# Lamp_Logic_Board_2.net
KiCad netlist of a schematic drawn in EAGLE
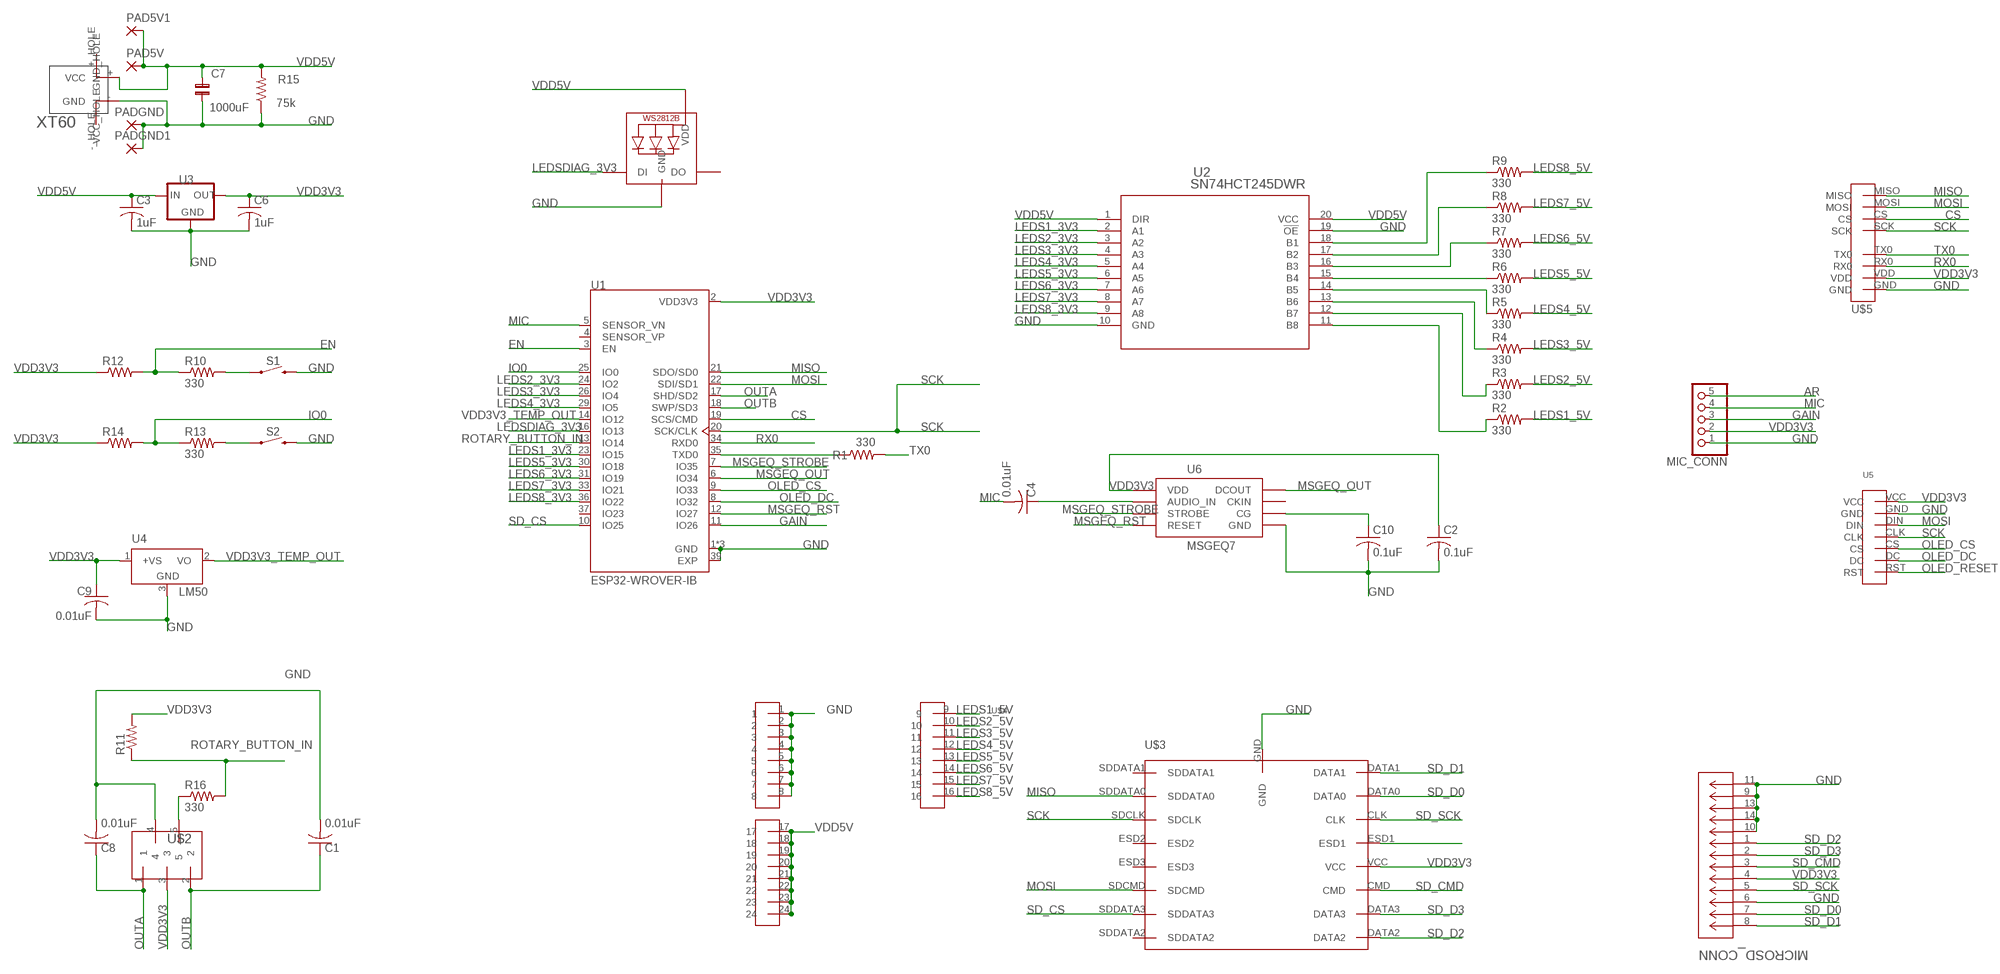
[diagram p0: schematic, sheet 1]

(export (version "E")
  (design (tool "Eeschema 10.0.6"))
  (components
    (comp (ref "C1")
      (value "0.01uF")
      (footprint "eagle-import:C0402")
      (libsource (lib "eagle-import") (part "C-USC0402"))
    )
    (comp (ref "C2")
      (value "0.1uF")
      (footprint "eagle-import:C0805")
      (libsource (lib "eagle-import") (part "C-USC0805"))
    )
    (comp (ref "C3")
      (value "1uF")
      (footprint "eagle-import:C0402")
      (libsource (lib "eagle-import") (part "C-USC0402"))
    )
    (comp (ref "C4")
      (value "0.01uF")
      (footprint "eagle-import:C0402")
      (libsource (lib "eagle-import") (part "C-USC0402"))
    )
    (comp (ref "C6")
      (value "1uF")
      (footprint "eagle-import:C0402")
      (libsource (lib "eagle-import") (part "C-USC0402"))
    )
    (comp (ref "C7")
      (value "1000uF")
      (footprint "eagle-import:ENP2,0-5")
      (libsource (lib "eagle-import") (part "C-BP-2,0X5"))
    )
    (comp (ref "C8")
      (value "0.01uF")
      (footprint "eagle-import:C0402")
      (libsource (lib "eagle-import") (part "C-USC0402"))
    )
    (comp (ref "C9")
      (value "0.01uF")
      (footprint "eagle-import:C0402")
      (libsource (lib "eagle-import") (part "C-USC0402"))
    )
    (comp (ref "C10")
      (value "0.1uF")
      (footprint "eagle-import:C0805")
      (libsource (lib "eagle-import") (part "C-USC0805"))
    )
    (comp (ref "LED1")
      (value "WS2812B5050")
      (footprint "eagle-import:WS2812B")
      (fields (field (name "MF") "Seeed Technology") (field (name "MP") "WS2812B"))
      (libsource (lib "eagle-import") (part "WS2812B5050"))
    )
    (comp (ref "MICROSD_CONN")
      (value "LLC")
      (footprint "eagle-import:CON00218_8")
      (libsource (lib "eagle-import") (part "LLC"))
    )
    (comp (ref "MIC_CONN")
      (value "PINHD-1X5")
      (footprint "eagle-import:1X05")
      (libsource (lib "eagle-import") (part "PINHD-1X5"))
    )
    (comp (ref "PAD5V")
      (value "SMD5")
      (footprint "eagle-import:SMD2,54-5,08")
      (libsource (lib "eagle-import") (part "SMD5"))
    )
    (comp (ref "PAD5V1")
      (value "SMD5")
      (footprint "eagle-import:SMD2,54-5,08")
      (libsource (lib "eagle-import") (part "SMD5"))
    )
    (comp (ref "PADGND")
      (value "SMD5")
      (footprint "eagle-import:SMD2,54-5,08")
      (libsource (lib "eagle-import") (part "SMD5"))
    )
    (comp (ref "PADGND1")
      (value "SMD5")
      (footprint "eagle-import:SMD2,54-5,08")
      (libsource (lib "eagle-import") (part "SMD5"))
    )
    (comp (ref "R1")
      (value "330")
      (footprint "eagle-import:R1206")
      (libsource (lib "eagle-import") (part "R-US_R1206"))
    )
    (comp (ref "R2")
      (value "330")
      (footprint "eagle-import:R1206")
      (libsource (lib "eagle-import") (part "R-US_R1206"))
    )
    (comp (ref "R3")
      (value "330")
      (footprint "eagle-import:R1206")
      (libsource (lib "eagle-import") (part "R-US_R1206"))
    )
    (comp (ref "R4")
      (value "330")
      (footprint "eagle-import:R1206")
      (libsource (lib "eagle-import") (part "R-US_R1206"))
    )
    (comp (ref "R5")
      (value "330")
      (footprint "eagle-import:R1206")
      (libsource (lib "eagle-import") (part "R-US_R1206"))
    )
    (comp (ref "R6")
      (value "330")
      (footprint "eagle-import:R1206")
      (libsource (lib "eagle-import") (part "R-US_R1206"))
    )
    (comp (ref "R7")
      (value "330")
      (footprint "eagle-import:R1206")
      (libsource (lib "eagle-import") (part "R-US_R1206"))
    )
    (comp (ref "R8")
      (value "330")
      (footprint "eagle-import:R1206")
      (libsource (lib "eagle-import") (part "R-US_R1206"))
    )
    (comp (ref "R9")
      (value "330")
      (footprint "eagle-import:R1206")
      (libsource (lib "eagle-import") (part "R-US_R1206"))
    )
    (comp (ref "R10")
      (value "330")
      (footprint "eagle-import:R1206")
      (libsource (lib "eagle-import") (part "R-US_R1206"))
    )
    (comp (ref "R11")
      (value "R-US_R0603")
      (footprint "eagle-import:R0603")
      (libsource (lib "eagle-import") (part "R-US_R0603"))
    )
    (comp (ref "R12")
      (value "R-US_R0603")
      (footprint "eagle-import:R0603")
      (libsource (lib "eagle-import") (part "R-US_R0603"))
    )
    (comp (ref "R13")
      (value "330")
      (footprint "eagle-import:R1206")
      (libsource (lib "eagle-import") (part "R-US_R1206"))
    )
    (comp (ref "R14")
      (value "R-US_R0603")
      (footprint "eagle-import:R0603")
      (libsource (lib "eagle-import") (part "R-US_R0603"))
    )
    (comp (ref "R15")
      (value "75k")
      (footprint "eagle-import:0309_12")
      (libsource (lib "eagle-import") (part "R-US_0309/12"))
    )
    (comp (ref "R16")
      (value "330")
      (footprint "eagle-import:R1206")
      (libsource (lib "eagle-import") (part "R-US_R1206"))
    )
    (comp (ref "S1")
      (value "MOMENTARY-SWITCH-SPST-SMD-6.0X3.5MM")
      (footprint "eagle-import:TACTILE_SWITCH_SMD_6.0X3.5MM")
      (libsource (lib "eagle-import") (part "MOMENTARY-SWITCH-SPST-SMD-6.0X3.5MM"))
    )
    (comp (ref "S2")
      (value "MOMENTARY-SWITCH-SPST-SMD-6.0X3.5MM")
      (footprint "eagle-import:TACTILE_SWITCH_SMD_6.0X3.5MM")
      (libsource (lib "eagle-import") (part "MOMENTARY-SWITCH-SPST-SMD-6.0X3.5MM"))
    )
    (comp (ref "U$1")
      (value "XT60")
      (footprint "eagle-import:XT60")
      (libsource (lib "eagle-import") (part "XT60"))
    )
    (comp (ref "U$2")
      (value "EN11-HSM1AF15")
      (footprint "eagle-import:EN11-HSM")
      (libsource (lib "eagle-import") (part "EN11-HSM1AF15"))
    )
    (comp (ref "U$3")
      (value "CM1624-08DE")
      (footprint "eagle-import:CM1624-08DE")
      (libsource (lib "eagle-import") (part "CM1624-08DE"))
    )
    (comp (ref "U$4")
      (value "3X8PINHEAD")
      (footprint "eagle-import:3X8PINHEAD")
      (libsource (lib "eagle-import") (part "3X8PINHEAD"))
    )
    (comp (ref "U$5")
      (value "2X4PINHEAD")
      (footprint "eagle-import:2X4PINHEAD")
      (libsource (lib "eagle-import") (part "2X4PINHEAD"))
    )
    (comp (ref "U1")
      (value "ESP32-WROVER-IB")
      (footprint "eagle-import:XCVR_ESP32-WROVER-I")
      (fields (field (name "MF") "Espressif Systems") (field (name "MP") "ESP32-WROVER-I"))
      (libsource (lib "eagle-import") (part "ESP32-WROVER-I"))
    )
    (comp (ref "U2")
      (value "SN74HCT245DWR")
      (footprint "eagle-import:DW20")
      (libsource (lib "eagle-import") (part "SN74HCT245DWR"))
    )
    (comp (ref "U3")
      (value "LM1117MP-1.8")
      (footprint "eagle-import:SOT223")
      (fields (field (name "MF") "Texas Instruments"))
      (libsource (lib "eagle-import") (part "LM1117?-MP1.8"))
    )
    (comp (ref "U4")
      (value "LM50")
      (footprint "eagle-import:SOT23")
      (libsource (lib "eagle-import") (part "LM50"))
    )
    (comp (ref "U5")
      (value "SPIOLED_STANDOFF")
      (footprint "eagle-import:SPIOLED_STADOFF")
      (libsource (lib "eagle-import") (part "SPIOLED_STANDOFF"))
    )
    (comp (ref "U6")
      (value "MSGEQ7DIL")
      (footprint "eagle-import:DIL-08")
      (fields
        (field (name "DIGI-KEY_PART_NUMBER") "1568-1544-ND")
        (field (name "MF") "SparkFun Electronics")
        (field (name "MP") "MSGEQ7")
      )
      (libsource (lib "eagle-import") (part "MSGEQ7DIL"))
    )
  )
  (nets
    (net (code "1") (name "/AR") (class "Default")
      (node (ref "MIC_CONN") (pin "5") (pinfunction "5_5") (pintype "passive"))
    )
    (net (code "2") (name "/CS") (class "Default")
      (node (ref "U$5") (pin "CS") (pinfunction "CS_CS") (pintype "bidirectional"))
      (node (ref "U1") (pin "19") (pinfunction "SCS/CMD_19") (pintype "bidirectional"))
    )
    (net (code "3") (name "/EN") (class "Default")
      (node (ref "R10") (pin "1") (pinfunction "1_1") (pintype "passive"))
      (node (ref "R12") (pin "2") (pinfunction "2_2") (pintype "passive"))
      (node (ref "U1") (pin "3") (pinfunction "EN_3") (pintype "input"))
    )
    (net (code "4") (name "/GAIN") (class "Default")
      (node (ref "MIC_CONN") (pin "3") (pinfunction "3_3") (pintype "passive"))
      (node (ref "U1") (pin "11") (pinfunction "IO26_11") (pintype "bidirectional"))
    )
    (net (code "5") (name "/GND") (class "Default")
      (node (ref "C1") (pin "2") (pinfunction "2_2") (pintype "passive"))
      (node (ref "C10") (pin "2") (pinfunction "2_2") (pintype "passive"))
      (node (ref "C2") (pin "2") (pinfunction "2_2") (pintype "passive"))
      (node (ref "C3") (pin "2") (pinfunction "2_2") (pintype "passive"))
      (node (ref "C6") (pin "2") (pinfunction "2_2") (pintype "passive"))
      (node (ref "C7") (pin "1") (pinfunction "1_1") (pintype "passive"))
      (node (ref "C8") (pin "2") (pinfunction "2_2") (pintype "passive"))
      (node (ref "C9") (pin "2") (pinfunction "2_2") (pintype "passive"))
      (node (ref "LED1") (pin "3-GND") (pinfunction "GND_3-GND") (pintype "power_in"))
      (node (ref "MICROSD_CONN") (pin "10") (pinfunction "10_10") (pintype "passive"))
      (node (ref "MICROSD_CONN") (pin "11") (pinfunction "11_11") (pintype "passive"))
      (node (ref "MICROSD_CONN") (pin "13") (pinfunction "13_13") (pintype "passive"))
      (node (ref "MICROSD_CONN") (pin "14") (pinfunction "14_14") (pintype "passive"))
      (node (ref "MICROSD_CONN") (pin "6") (pinfunction "6_6") (pintype "passive"))
      (node (ref "MICROSD_CONN") (pin "9") (pinfunction "9_9") (pintype "passive"))
      (node (ref "MIC_CONN") (pin "1") (pinfunction "1_1") (pintype "passive"))
      (node (ref "PADGND") (pin "1") (pinfunction "P_1") (pintype "passive"))
      (node (ref "PADGND1") (pin "1") (pinfunction "P_1") (pintype "passive"))
      (node (ref "R15") (pin "1") (pinfunction "1_1") (pintype "passive"))
      (node (ref "S1") (pin "2") (pinfunction "2_2") (pintype "passive"))
      (node (ref "S2") (pin "2") (pinfunction "2_2") (pintype "passive"))
      (node (ref "U$1") (pin "-") (pinfunction "GND_-") (pintype "bidirectional"))
      (node (ref "U$2") (pin "4") (pinfunction "4_4") (pintype "bidirectional"))
      (node (ref "U$3") (pin "GND") (pinfunction "GND_GND") (pintype "bidirectional"))
      (node (ref "U$4") (pin "1") (pinfunction "1_1") (pintype "bidirectional"))
      (node (ref "U$4") (pin "2") (pinfunction "2_2") (pintype "bidirectional"))
      (node (ref "U$4") (pin "3") (pinfunction "3_3") (pintype "bidirectional"))
      (node (ref "U$4") (pin "4") (pinfunction "4_4") (pintype "bidirectional"))
      (node (ref "U$4") (pin "5") (pinfunction "5_5") (pintype "bidirectional"))
      (node (ref "U$4") (pin "6") (pinfunction "6_6") (pintype "bidirectional"))
      (node (ref "U$4") (pin "7") (pinfunction "7_7") (pintype "bidirectional"))
      (node (ref "U$4") (pin "8") (pinfunction "8_8") (pintype "bidirectional"))
      (node (ref "U$5") (pin "GND") (pinfunction "GND_GND") (pintype "bidirectional"))
      (node (ref "U1") (pin "1") (pinfunction "GND_1") (pintype "power_in"))
      (node (ref "U1") (pin "15") (pinfunction "GND_15") (pintype "power_in"))
      (node (ref "U1") (pin "38") (pinfunction "GND_38") (pintype "power_in"))
      (node (ref "U1") (pin "39") (pinfunction "EXP_39") (pintype "power_in"))
      (node (ref "U2") (pin "10") (pinfunction "GND_10") (pintype "power_in"))
      (node (ref "U2") (pin "19") (pinfunction "~{OE}_19") (pintype "input"))
      (node (ref "U3") (pin "1") (pinfunction "GND_1") (pintype "input"))
      (node (ref "U4") (pin "3") (pinfunction "GND_3") (pintype "power_in"))
      (node (ref "U5") (pin "GND") (pinfunction "GND_GND") (pintype "bidirectional"))
      (node (ref "U6") (pin "2") (pinfunction "GND_2") (pintype "bidirectional"))
    )
    (net (code "6") (name "/IO0") (class "Default")
      (node (ref "R13") (pin "1") (pinfunction "1_1") (pintype "passive"))
      (node (ref "R14") (pin "2") (pinfunction "2_2") (pintype "passive"))
      (node (ref "U1") (pin "25") (pinfunction "IO0_25") (pintype "bidirectional"))
    )
    (net (code "7") (name "/LEDS1_3V3") (class "Default")
      (node (ref "U1") (pin "23") (pinfunction "IO15_23") (pintype "bidirectional"))
      (node (ref "U2") (pin "2") (pinfunction "A1_2") (pintype "bidirectional"))
    )
    (net (code "8") (name "/LEDS1_5V") (class "Default")
      (node (ref "R2") (pin "2") (pinfunction "2_2") (pintype "passive"))
      (node (ref "U$4") (pin "9") (pinfunction "9_9") (pintype "bidirectional"))
    )
    (net (code "9") (name "/LEDS2_3V3") (class "Default")
      (node (ref "U1") (pin "24") (pinfunction "IO2_24") (pintype "bidirectional"))
      (node (ref "U2") (pin "3") (pinfunction "A2_3") (pintype "bidirectional"))
    )
    (net (code "10") (name "/LEDS2_5V") (class "Default")
      (node (ref "R3") (pin "2") (pinfunction "2_2") (pintype "passive"))
      (node (ref "U$4") (pin "10") (pinfunction "10_10") (pintype "bidirectional"))
    )
    (net (code "11") (name "/LEDS3_3V3") (class "Default")
      (node (ref "U1") (pin "26") (pinfunction "IO4_26") (pintype "bidirectional"))
      (node (ref "U2") (pin "4") (pinfunction "A3_4") (pintype "bidirectional"))
    )
    (net (code "12") (name "/LEDS3_5V") (class "Default")
      (node (ref "R4") (pin "2") (pinfunction "2_2") (pintype "passive"))
      (node (ref "U$4") (pin "11") (pinfunction "11_11") (pintype "bidirectional"))
    )
    (net (code "13") (name "/LEDS4_3V3") (class "Default")
      (node (ref "U1") (pin "29") (pinfunction "IO5_29") (pintype "bidirectional"))
      (node (ref "U2") (pin "5") (pinfunction "A4_5") (pintype "bidirectional"))
    )
    (net (code "14") (name "/LEDS4_5V") (class "Default")
      (node (ref "R5") (pin "2") (pinfunction "2_2") (pintype "passive"))
      (node (ref "U$4") (pin "12") (pinfunction "12_12") (pintype "bidirectional"))
    )
    (net (code "15") (name "/LEDS5_3V3") (class "Default")
      (node (ref "U1") (pin "30") (pinfunction "IO18_30") (pintype "bidirectional"))
      (node (ref "U2") (pin "6") (pinfunction "A5_6") (pintype "bidirectional"))
    )
    (net (code "16") (name "/LEDS5_5V") (class "Default")
      (node (ref "R6") (pin "2") (pinfunction "2_2") (pintype "passive"))
      (node (ref "U$4") (pin "13") (pinfunction "13_13") (pintype "bidirectional"))
    )
    (net (code "17") (name "/LEDS6_3V3") (class "Default")
      (node (ref "U1") (pin "31") (pinfunction "IO19_31") (pintype "bidirectional"))
      (node (ref "U2") (pin "7") (pinfunction "A6_7") (pintype "bidirectional"))
    )
    (net (code "18") (name "/LEDS6_5V") (class "Default")
      (node (ref "R7") (pin "2") (pinfunction "2_2") (pintype "passive"))
      (node (ref "U$4") (pin "14") (pinfunction "14_14") (pintype "bidirectional"))
    )
    (net (code "19") (name "/LEDS7_3V3") (class "Default")
      (node (ref "U1") (pin "33") (pinfunction "IO21_33") (pintype "bidirectional"))
      (node (ref "U2") (pin "8") (pinfunction "A7_8") (pintype "bidirectional"))
    )
    (net (code "20") (name "/LEDS7_5V") (class "Default")
      (node (ref "R8") (pin "2") (pinfunction "2_2") (pintype "passive"))
      (node (ref "U$4") (pin "15") (pinfunction "15_15") (pintype "bidirectional"))
    )
    (net (code "21") (name "/LEDS8_3V3") (class "Default")
      (node (ref "U1") (pin "36") (pinfunction "IO22_36") (pintype "bidirectional"))
      (node (ref "U2") (pin "9") (pinfunction "A8_9") (pintype "bidirectional"))
    )
    (net (code "22") (name "/LEDS8_5V") (class "Default")
      (node (ref "R9") (pin "2") (pinfunction "2_2") (pintype "passive"))
      (node (ref "U$4") (pin "16") (pinfunction "16_16") (pintype "bidirectional"))
    )
    (net (code "23") (name "/LEDSDIAG_3V3") (class "Default")
      (node (ref "LED1") (pin "4-DIN") (pinfunction "DI_4-DIN") (pintype "input"))
      (node (ref "U1") (pin "16") (pinfunction "IO13_16") (pintype "bidirectional"))
    )
    (net (code "24") (name "/MIC") (class "Default")
      (node (ref "C4") (pin "2") (pinfunction "2_2") (pintype "passive"))
      (node (ref "MIC_CONN") (pin "4") (pinfunction "4_4") (pintype "passive"))
      (node (ref "U1") (pin "5") (pinfunction "SENSOR_VN_5") (pintype "input"))
    )
    (net (code "25") (name "/MISO") (class "Default")
      (node (ref "U$3") (pin "SDDATA0") (pinfunction "SDDATA0_SDDATA0") (pintype "bidirectional"))
      (node (ref "U$5") (pin "MISO") (pinfunction "MISO_MISO") (pintype "bidirectional"))
      (node (ref "U1") (pin "21") (pinfunction "SDO/SD0_21") (pintype "bidirectional"))
    )
    (net (code "26") (name "/MOSI") (class "Default")
      (node (ref "U$3") (pin "SDCMD") (pinfunction "SDCMD_SDCMD") (pintype "bidirectional"))
      (node (ref "U$5") (pin "MOSI") (pinfunction "MOSI_MOSI") (pintype "bidirectional"))
      (node (ref "U1") (pin "22") (pinfunction "SDI/SD1_22") (pintype "bidirectional"))
      (node (ref "U5") (pin "DIN") (pinfunction "DIN_DIN") (pintype "bidirectional"))
    )
    (net (code "27") (name "/MSGEQ_OUT") (class "Default")
      (node (ref "U1") (pin "6") (pinfunction "IO34_6") (pintype "input"))
      (node (ref "U6") (pin "3") (pinfunction "DCOUT_3") (pintype "bidirectional"))
    )
    (net (code "28") (name "/MSGEQ_RST") (class "Default")
      (node (ref "U1") (pin "12") (pinfunction "IO27_12") (pintype "bidirectional"))
      (node (ref "U6") (pin "7") (pinfunction "RESET_7") (pintype "input"))
    )
    (net (code "29") (name "/MSGEQ_STROBE") (class "Default")
      (node (ref "U1") (pin "7") (pinfunction "IO35_7") (pintype "input"))
      (node (ref "U6") (pin "4") (pinfunction "STROBE_4") (pintype "input"))
    )
    (net (code "30") (name "/OLED_CS") (class "Default")
      (node (ref "U1") (pin "9") (pinfunction "IO33_9") (pintype "bidirectional"))
      (node (ref "U5") (pin "CS") (pinfunction "CS_CS") (pintype "bidirectional"))
    )
    (net (code "31") (name "/OLED_DC") (class "Default")
      (node (ref "U1") (pin "8") (pinfunction "IO32_8") (pintype "bidirectional"))
      (node (ref "U5") (pin "DC") (pinfunction "DC_DC") (pintype "bidirectional"))
    )
    (net (code "32") (name "/OLED_RESET") (class "Default")
      (node (ref "U5") (pin "RST") (pinfunction "RST_RST") (pintype "bidirectional"))
    )
    (net (code "33") (name "/OUTA") (class "Default")
      (node (ref "C8") (pin "1") (pinfunction "1_1") (pintype "passive"))
      (node (ref "U$2") (pin "1") (pinfunction "1_1") (pintype "passive"))
      (node (ref "U1") (pin "17") (pinfunction "SHD/SD2_17") (pintype "bidirectional"))
    )
    (net (code "34") (name "/OUTB") (class "Default")
      (node (ref "C1") (pin "1") (pinfunction "1_1") (pintype "passive"))
      (node (ref "U$2") (pin "2") (pinfunction "2_2") (pintype "passive"))
      (node (ref "U1") (pin "18") (pinfunction "SWP/SD3_18") (pintype "bidirectional"))
    )
    (net (code "35") (name "/ROTARY_BUTTON_IN") (class "Default")
      (node (ref "R11") (pin "1") (pinfunction "1_1") (pintype "passive"))
      (node (ref "R16") (pin "2") (pinfunction "2_2") (pintype "passive"))
      (node (ref "U1") (pin "13") (pinfunction "IO14_13") (pintype "bidirectional"))
    )
    (net (code "36") (name "/RX0") (class "Default")
      (node (ref "U$5") (pin "RX0") (pinfunction "RX0_RX0") (pintype "bidirectional"))
      (node (ref "U1") (pin "34") (pinfunction "RXD0_34") (pintype "bidirectional"))
    )
    (net (code "37") (name "/SCK") (class "Default")
      (node (ref "U$3") (pin "SDCLK") (pinfunction "SDCLK_SDCLK") (pintype "bidirectional"))
      (node (ref "U$5") (pin "SCK") (pinfunction "SCK_SCK") (pintype "bidirectional"))
      (node (ref "U1") (pin "20") (pinfunction "SCK/CLK_20") (pintype "bidirectional"))
      (node (ref "U5") (pin "CLK") (pinfunction "CLK_CLK") (pintype "bidirectional"))
    )
    (net (code "38") (name "/SD_CMD") (class "Default")
      (node (ref "MICROSD_CONN") (pin "3") (pinfunction "3_3") (pintype "passive"))
      (node (ref "U$3") (pin "CMD") (pinfunction "CMD_CMD") (pintype "bidirectional"))
    )
    (net (code "39") (name "/SD_CS") (class "Default")
      (node (ref "U$3") (pin "SDDATA3") (pinfunction "SDDATA3_SDDATA3") (pintype "bidirectional"))
      (node (ref "U1") (pin "10") (pinfunction "IO25_10") (pintype "bidirectional"))
    )
    (net (code "40") (name "/SD_D0") (class "Default")
      (node (ref "MICROSD_CONN") (pin "7") (pinfunction "7_7") (pintype "passive"))
      (node (ref "U$3") (pin "DATA0") (pinfunction "DATA0_DATA0") (pintype "bidirectional"))
    )
    (net (code "41") (name "/SD_D1") (class "Default")
      (node (ref "MICROSD_CONN") (pin "8") (pinfunction "8_8") (pintype "passive"))
      (node (ref "U$3") (pin "DATA1") (pinfunction "DATA1_DATA1") (pintype "bidirectional"))
    )
    (net (code "42") (name "/SD_D2") (class "Default")
      (node (ref "MICROSD_CONN") (pin "1") (pinfunction "1_1") (pintype "passive"))
      (node (ref "U$3") (pin "DATA2") (pinfunction "DATA2_DATA2") (pintype "bidirectional"))
    )
    (net (code "43") (name "/SD_D3") (class "Default")
      (node (ref "MICROSD_CONN") (pin "2") (pinfunction "2_2") (pintype "passive"))
      (node (ref "U$3") (pin "DATA3") (pinfunction "DATA3_DATA3") (pintype "bidirectional"))
    )
    (net (code "44") (name "/SD_SCK") (class "Default")
      (node (ref "MICROSD_CONN") (pin "5") (pinfunction "5_5") (pintype "passive"))
      (node (ref "U$3") (pin "CLK") (pinfunction "CLK_CLK") (pintype "bidirectional"))
    )
    (net (code "45") (name "/TX0") (class "Default")
      (node (ref "R1") (pin "2") (pinfunction "2_2") (pintype "passive"))
      (node (ref "U$5") (pin "TX0") (pinfunction "TX0_TX0") (pintype "bidirectional"))
    )
    (net (code "46") (name "/VDD3V3") (class "Default")
      (node (ref "C2") (pin "1") (pinfunction "1_1") (pintype "passive"))
      (node (ref "C6") (pin "1") (pinfunction "1_1") (pintype "passive"))
      (node (ref "C9") (pin "1") (pinfunction "1_1") (pintype "passive"))
      (node (ref "MICROSD_CONN") (pin "4") (pinfunction "4_4") (pintype "passive"))
      (node (ref "MIC_CONN") (pin "2") (pinfunction "2_2") (pintype "passive"))
      (node (ref "R11") (pin "2") (pinfunction "2_2") (pintype "passive"))
      (node (ref "R12") (pin "1") (pinfunction "1_1") (pintype "passive"))
      (node (ref "R14") (pin "1") (pinfunction "1_1") (pintype "passive"))
      (node (ref "U$2") (pin "3") (pinfunction "3_3") (pintype "passive"))
      (node (ref "U$3") (pin "VCC") (pinfunction "VCC_VCC") (pintype "bidirectional"))
      (node (ref "U$5") (pin "VDD") (pinfunction "VDD_VDD") (pintype "bidirectional"))
      (node (ref "U1") (pin "2") (pinfunction "VDD3V3_2") (pintype "power_in"))
      (node (ref "U3") (pin "2") (pinfunction "OUT_2") (pintype "passive"))
      (node (ref "U3") (pin "4") (pinfunction "OUT_4") (pintype "passive"))
      (node (ref "U4") (pin "1") (pinfunction "+VS_1") (pintype "input"))
      (node (ref "U5") (pin "VCC") (pinfunction "VCC_VCC") (pintype "bidirectional"))
      (node (ref "U6") (pin "1") (pinfunction "VDD_1") (pintype "input"))
    )
    (net (code "47") (name "/VDD3V3_TEMP_OUT") (class "Default")
      (node (ref "U1") (pin "14") (pinfunction "IO12_14") (pintype "bidirectional"))
      (node (ref "U4") (pin "2") (pinfunction "VO_2") (pintype "input"))
    )
    (net (code "48") (name "/VDD5V") (class "Default")
      (node (ref "C3") (pin "1") (pinfunction "1_1") (pintype "passive"))
      (node (ref "C7") (pin "2") (pinfunction "2_2") (pintype "passive"))
      (node (ref "LED1") (pin "1-VDD") (pinfunction "VDD_1-VDD") (pintype "power_in"))
      (node (ref "PAD5V") (pin "1") (pinfunction "P_1") (pintype "passive"))
      (node (ref "PAD5V1") (pin "1") (pinfunction "P_1") (pintype "passive"))
      (node (ref "R15") (pin "2") (pinfunction "2_2") (pintype "passive"))
      (node (ref "U$1") (pin "+") (pinfunction "VCC_+") (pintype "bidirectional"))
      (node (ref "U$4") (pin "17") (pinfunction "17_17") (pintype "bidirectional"))
      (node (ref "U$4") (pin "18") (pinfunction "18_18") (pintype "bidirectional"))
      (node (ref "U$4") (pin "19") (pinfunction "19_19") (pintype "bidirectional"))
      (node (ref "U$4") (pin "20") (pinfunction "20_20") (pintype "bidirectional"))
      (node (ref "U$4") (pin "21") (pinfunction "21_21") (pintype "bidirectional"))
      (node (ref "U$4") (pin "22") (pinfunction "22_22") (pintype "bidirectional"))
      (node (ref "U$4") (pin "23") (pinfunction "23_23") (pintype "bidirectional"))
      (node (ref "U$4") (pin "24") (pinfunction "24_24") (pintype "bidirectional"))
      (node (ref "U2") (pin "1") (pinfunction "DIR_1") (pintype "input"))
      (node (ref "U2") (pin "20") (pinfunction "VCC_20") (pintype "power_in"))
      (node (ref "U3") (pin "3") (pinfunction "IN_3") (pintype "input"))
    )
    (net (code "49") (name "Net-(R10-Pad2)") (class "Default")
      (node (ref "R10") (pin "2") (pinfunction "2_2") (pintype "passive"))
      (node (ref "S1") (pin "1") (pinfunction "1_1") (pintype "passive"))
    )
    (net (code "50") (name "Net-(R13-Pad2)") (class "Default")
      (node (ref "R13") (pin "2") (pinfunction "2_2") (pintype "passive"))
      (node (ref "S2") (pin "1") (pinfunction "1_1") (pintype "passive"))
    )
    (net (code "51") (name "Net-(R16-Pad1)") (class "Default")
      (node (ref "R16") (pin "1") (pinfunction "1_1") (pintype "passive"))
      (node (ref "U$2") (pin "5") (pinfunction "5_5") (pintype "bidirectional"))
    )
    (net (code "52") (name "Net-(U1-TXD0)") (class "Default")
      (node (ref "R1") (pin "1") (pinfunction "1_1") (pintype "passive"))
      (node (ref "U1") (pin "35") (pinfunction "TXD0_35") (pintype "bidirectional"))
    )
    (net (code "53") (name "Net-(U2-B1)") (class "Default")
      (node (ref "R9") (pin "1") (pinfunction "1_1") (pintype "passive"))
      (node (ref "U2") (pin "18") (pinfunction "B1_18") (pintype "bidirectional"))
    )
    (net (code "54") (name "Net-(U2-B2)") (class "Default")
      (node (ref "R8") (pin "1") (pinfunction "1_1") (pintype "passive"))
      (node (ref "U2") (pin "17") (pinfunction "B2_17") (pintype "bidirectional"))
    )
    (net (code "55") (name "Net-(U2-B3)") (class "Default")
      (node (ref "R7") (pin "1") (pinfunction "1_1") (pintype "passive"))
      (node (ref "U2") (pin "16") (pinfunction "B3_16") (pintype "bidirectional"))
    )
    (net (code "56") (name "Net-(U2-B4)") (class "Default")
      (node (ref "R6") (pin "1") (pinfunction "1_1") (pintype "passive"))
      (node (ref "U2") (pin "15") (pinfunction "B4_15") (pintype "bidirectional"))
    )
    (net (code "57") (name "Net-(U2-B5)") (class "Default")
      (node (ref "R5") (pin "1") (pinfunction "1_1") (pintype "passive"))
      (node (ref "U2") (pin "14") (pinfunction "B5_14") (pintype "bidirectional"))
    )
    (net (code "58") (name "Net-(U2-B6)") (class "Default")
      (node (ref "R4") (pin "1") (pinfunction "1_1") (pintype "passive"))
      (node (ref "U2") (pin "13") (pinfunction "B6_13") (pintype "bidirectional"))
    )
    (net (code "59") (name "Net-(U2-B7)") (class "Default")
      (node (ref "R3") (pin "1") (pinfunction "1_1") (pintype "passive"))
      (node (ref "U2") (pin "12") (pinfunction "B7_12") (pintype "bidirectional"))
    )
    (net (code "60") (name "Net-(U2-B8)") (class "Default")
      (node (ref "R2") (pin "1") (pinfunction "1_1") (pintype "passive"))
      (node (ref "U2") (pin "11") (pinfunction "B8_11") (pintype "bidirectional"))
    )
    (net (code "61") (name "Net-(U6-AUDIO_IN)") (class "Default")
      (node (ref "C4") (pin "1") (pinfunction "1_1") (pintype "passive"))
      (node (ref "U6") (pin "5") (pinfunction "AUDIO_IN_5") (pintype "input"))
    )
    (net (code "62") (name "Net-(U6-CG)") (class "Default")
      (node (ref "C10") (pin "1") (pinfunction "1_1") (pintype "passive"))
      (node (ref "U6") (pin "6") (pinfunction "CG_6") (pintype "bidirectional"))
    )
    (net (code "63") (name "unconnected-(LED1-DO-Pad2-DOUT)") (class "Default")
      (node (ref "LED1") (pin "2-DOUT") (pinfunction "DO_2-DOUT") (pintype "output"))
    )
    (net (code "64") (name "unconnected-(U$1-GND_HOLE-Pad-_HOLE)") (class "Default")
      (node (ref "U$1") (pin "-_HOLE") (pinfunction "GND_HOLE_-_HOLE") (pintype "bidirectional"))
    )
    (net (code "65") (name "unconnected-(U$1-VCC_HOLE-Pad+_HOLE)") (class "Default")
      (node (ref "U$1") (pin "+_HOLE") (pinfunction "VCC_HOLE_+_HOLE") (pintype "bidirectional"))
    )
    (net (code "66") (name "unconnected-(U$3-PadESD1)") (class "Default")
      (node (ref "U$3") (pin "ESD1") (pinfunction "ESD1_ESD1") (pintype "bidirectional"))
    )
    (net (code "67") (name "unconnected-(U$3-PadESD2)") (class "Default")
      (node (ref "U$3") (pin "ESD2") (pinfunction "ESD2_ESD2") (pintype "bidirectional"))
    )
    (net (code "68") (name "unconnected-(U$3-PadESD3)") (class "Default")
      (node (ref "U$3") (pin "ESD3") (pinfunction "ESD3_ESD3") (pintype "bidirectional"))
    )
    (net (code "69") (name "unconnected-(U$3-PadSDDATA1)") (class "Default")
      (node (ref "U$3") (pin "SDDATA1") (pinfunction "SDDATA1_SDDATA1") (pintype "bidirectional"))
    )
    (net (code "70") (name "unconnected-(U$3-PadSDDATA2)") (class "Default")
      (node (ref "U$3") (pin "SDDATA2") (pinfunction "SDDATA2_SDDATA2") (pintype "bidirectional"))
    )
    (net (code "71") (name "unconnected-(U1-IO23-Pad37)") (class "Default")
      (node (ref "U1") (pin "37") (pinfunction "IO23_37") (pintype "bidirectional"))
    )
    (net (code "72") (name "unconnected-(U1-SENSOR_VP-Pad4)") (class "Default")
      (node (ref "U1") (pin "4") (pinfunction "SENSOR_VP_4") (pintype "input"))
    )
    (net (code "73") (name "unconnected-(U6-CKIN-Pad8)") (class "Default")
      (node (ref "U6") (pin "8") (pinfunction "CKIN_8") (pintype "bidirectional"))
    )
  )
)
